# 2019_v1_2.net
KiCad netlist of a schematic drawn in Altium Designer
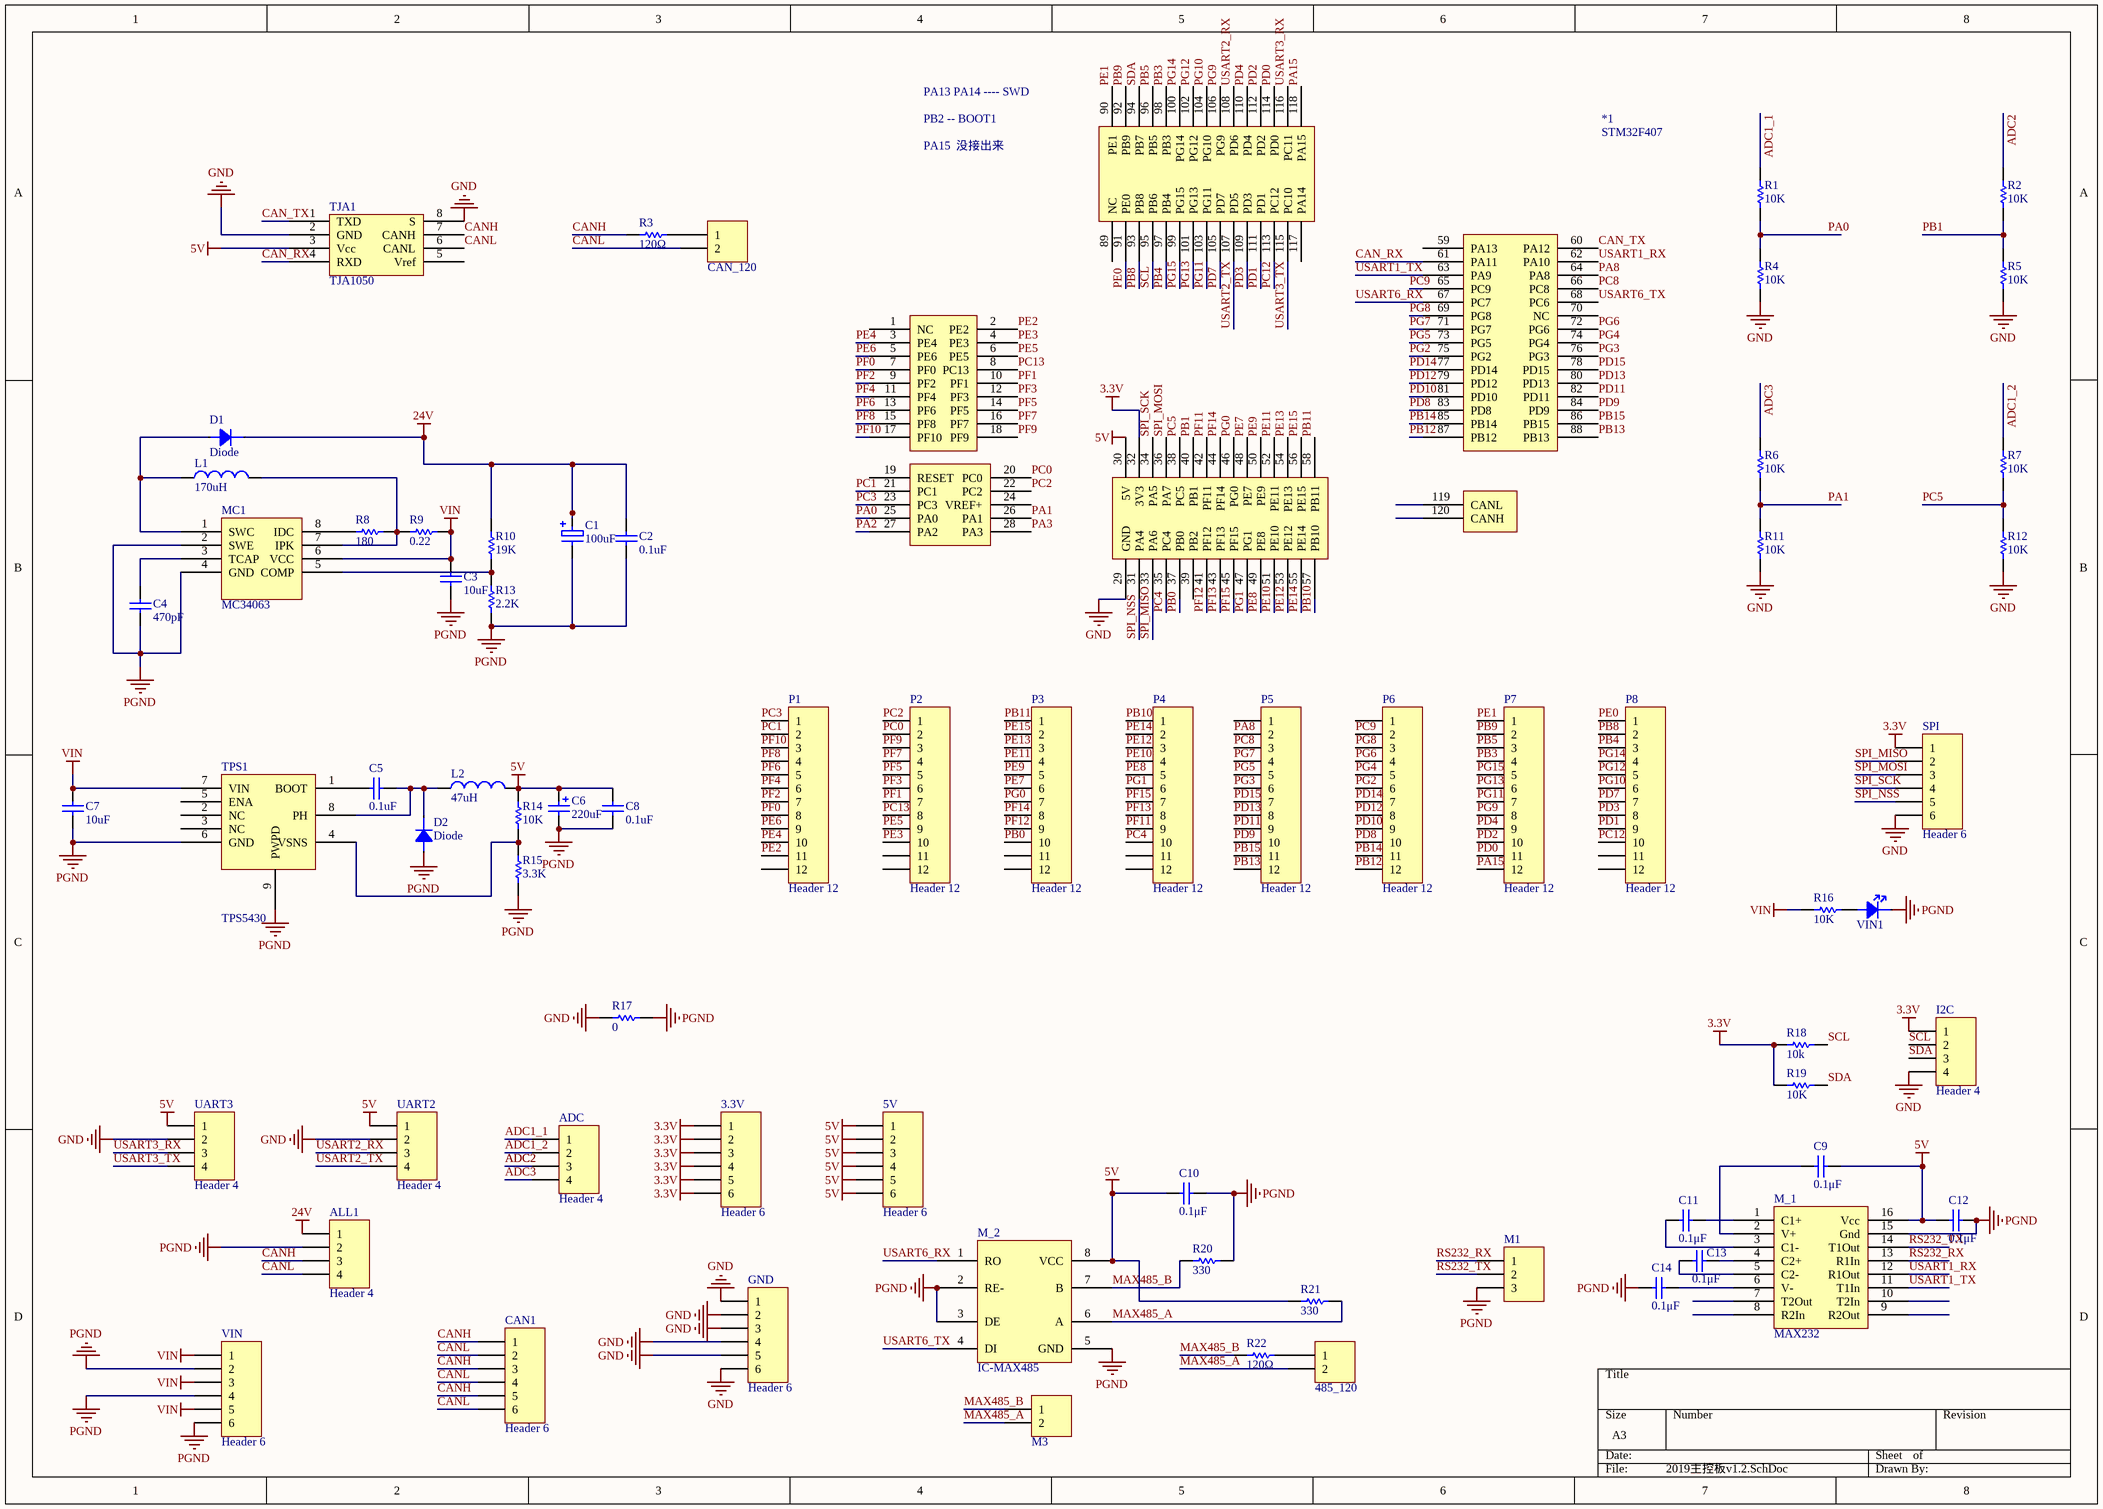
[diagram p0: 2019主控板v1.2.SchDoc]

(export (version "E")
  (design (tool "Eeschema 10.0.6"))
  (components
    (comp (ref "*1")
      (value "STM32F407")
      (footprint "STM32F407")
      (libsource (lib "K60-mainboard-v3.1") (part "STM32F407"))
    )
    (comp (ref "3.3V")
      (value "Header 6")
      (footprint "XH-2.54PIN6")
      (description "Header, 6-Pin")
      (fields (field (name "PUBLISHER") "Altium Limited"))
      (libsource (lib "Libraries_2014_0618") (part "Header 6"))
    )
    (comp (ref "5V")
      (value "Header 6")
      (footprint "XH-2.54PIN6")
      (description "Header, 6-Pin")
      (fields (field (name "PUBLISHER") "Altium Limited"))
      (libsource (lib "Libraries_2014_0618") (part "Header 6"))
    )
    (comp (ref "485_120")
      (value "Header 2")
      (footprint "SIP2")
      (description "Header, 2-Pin")
      (fields (field (name "PUBLISHER") "Altium Limited"))
      (libsource (lib "Libraries_2014_0618") (part "Header 2"))
    )
    (comp (ref "ADC")
      (value "Header 4")
      (footprint "XH-2.54pin4")
      (description "Header, 4-Pin")
      (fields (field (name "PUBLISHER") "Altium Limited"))
      (libsource (lib "Libraries_2014_0618") (part "Header 4"))
    )
    (comp (ref "ALL1")
      (value "Header 4")
      (footprint "XH-2.54pin4")
      (description "Header, 4-Pin")
      (fields (field (name "PUBLISHER") "Altium Limited"))
      (libsource (lib "Libraries_2014_0618") (part "Header 4"))
    )
    (comp (ref "C1")
      (value "100uF")
      (footprint "C_ELE")
      (description "电解电容")
      (fields (field (name "PUBLISHER") "Altium Limited"))
      (libsource (lib "Libraries_2014_0618") (part "CAP-ELE"))
    )
    (comp (ref "C2")
      (value "0.1uF")
      (footprint "CAP-MLCC-0603")
      (description "Capacitor")
      (fields (field (name "Comment") "Cap") (field (name "PUBLISHER") "Altium Limited"))
      (libsource (lib "K60-mainboard-v3.1") (part "Cap"))
    )
    (comp (ref "C3")
      (value "10uF")
      (footprint "0805C")
      (description "Capacitor")
      (fields (field (name "Comment") "Cap") (field (name "PUBLISHER") "Altium Limited"))
      (libsource (lib "K60-mainboard-v3.1") (part "Cap"))
    )
    (comp (ref "C4")
      (value "470pF")
      (footprint "CAP-MLCC-0603")
      (description "Capacitor")
      (fields (field (name "Comment") "Cap") (field (name "PUBLISHER") "Altium Limited"))
      (libsource (lib "K60-mainboard-v3.1") (part "Cap"))
    )
    (comp (ref "C5")
      (value "0.1uF")
      (footprint "CAP-MLCC-0603")
      (description "Capacitor")
      (fields (field (name "Comment") "Cap") (field (name "PUBLISHER") "Altium Limited"))
      (libsource (lib "K60-mainboard-v3.1") (part "Cap"))
    )
    (comp (ref "C6")
      (value "220uF")
      (footprint "CAP-TAN-7343/CAPD")
      (description "Polarized Capacitor (Radial)")
      (fields (field (name "Comment") "Cap Pol1") (field (name "PUBLISHER") "Altium Limited"))
      (libsource (lib "K60-mainboard-v3.1") (part "Cap Pol1"))
    )
    (comp (ref "C7")
      (value "10uF")
      (footprint "0805C")
      (description "Capacitor")
      (fields (field (name "Comment") "Cap") (field (name "PUBLISHER") "Altium Limited"))
      (libsource (lib "K60-mainboard-v3.1") (part "Cap"))
    )
    (comp (ref "C8")
      (value "0.1uF")
      (footprint "CAP-MLCC-0603")
      (description "Capacitor")
      (fields (field (name "Comment") "Cap") (field (name "PUBLISHER") "Altium Limited"))
      (libsource (lib "K60-mainboard-v3.1") (part "Cap"))
    )
    (comp (ref "C9")
      (value "0.1μF")
      (footprint "CAP-MLCC-0603")
      (description "无极性电容")
      (fields (field (name "PUBLISHER") "Altium Limited"))
      (libsource (lib "Libraries_2014_0618") (part "CAP"))
    )
    (comp (ref "C10")
      (value "0.1μF")
      (footprint "CAP-MLCC-0603")
      (description "无极性电容")
      (fields (field (name "PUBLISHER") "Altium Limited"))
      (libsource (lib "Libraries_2014_0618") (part "CAP"))
    )
    (comp (ref "C11")
      (value "0.1μF")
      (footprint "CAP-MLCC-0603")
      (description "无极性电容")
      (fields (field (name "PUBLISHER") "Altium Limited"))
      (libsource (lib "Libraries_2014_0618") (part "CAP"))
    )
    (comp (ref "C12")
      (value "0.1μF")
      (footprint "CAP-MLCC-0603")
      (description "无极性电容")
      (fields (field (name "PUBLISHER") "Altium Limited"))
      (libsource (lib "Libraries_2014_0618") (part "CAP"))
    )
    (comp (ref "C13")
      (value "0.1μF")
      (footprint "CAP-MLCC-0603")
      (description "无极性电容")
      (fields (field (name "PUBLISHER") "Altium Limited"))
      (libsource (lib "Libraries_2014_0618") (part "CAP"))
    )
    (comp (ref "C14")
      (value "0.1μF")
      (footprint "CAP-MLCC-0603")
      (description "无极性电容")
      (fields (field (name "PUBLISHER") "Altium Limited"))
      (libsource (lib "Libraries_2014_0618") (part "CAP"))
    )
    (comp (ref "CAN1")
      (value "Header 6")
      (footprint "Green_6P")
      (description "Header, 6-Pin")
      (fields (field (name "PUBLISHER") "Altium Limited"))
      (libsource (lib "Libraries_2014_0618") (part "Header 6"))
    )
    (comp (ref "CAN_120")
      (value "Header 2")
      (footprint "SIP2")
      (description "Header, 2-Pin")
      (fields (field (name "PUBLISHER") "Altium Limited"))
      (libsource (lib "Libraries_2014_0618") (part "Header 2"))
    )
    (comp (ref "D1") (value "Diode") (footprint "SS34") (libsource (lib "K60-mainboard-v3.1") (part "Diode")))
    (comp (ref "D2") (value "Diode") (footprint "SS34") (libsource (lib "K60-mainboard-v3.1") (part "Diode")))
    (comp (ref "GND")
      (value "Header 6")
      (footprint "XH-2.54PIN6")
      (description "Header, 6-Pin")
      (fields (field (name "PUBLISHER") "Altium Limited"))
      (libsource (lib "Libraries_2014_0618") (part "Header 6"))
    )
    (comp (ref "I2C")
      (value "Header 4")
      (footprint "XH-2.54pin4")
      (description "Header, 4-Pin")
      (fields (field (name "PUBLISHER") "Altium Limited"))
      (libsource (lib "Libraries_2014_0618") (part "Header 4"))
    )
    (comp (ref "L1")
      (value "170uH")
      (footprint "CD74")
      (description "Inductor")
      (fields (field (name "PUBLISHER") "Altium Limited"))
      (libsource (lib "smartcar_example") (part "Inductor"))
    )
    (comp (ref "L2")
      (value "47uH")
      (footprint "CD74")
      (description "Inductor")
      (fields (field (name "PUBLISHER") "Altium Limited"))
      (libsource (lib "smartcar_example") (part "Inductor"))
    )
    (comp (ref "M1")
      (value "Header 3")
      (footprint "Green_3P")
      (description "Header, 3-Pin")
      (fields (field (name "PUBLISHER") "Altium Limited"))
      (libsource (lib "Libraries_2014_0618") (part "Header 3"))
    )
    (comp (ref "M3")
      (value "Header 2")
      (footprint "Green_2P")
      (description "Header, 2-Pin")
      (fields (field (name "PUBLISHER") "Altium Limited"))
      (libsource (lib "Libraries_2014_0618") (part "Header 2"))
    )
    (comp (ref "MC1")
      (value "MC34063")
      (footprint "SO8")
      (libsource (lib "K60-mainboard-v3.1") (part "MC34063"))
    )
    (comp (ref "M_1")
      (value "MAX232")
      (footprint "SO-16_M")
      (libsource (lib "Libraries_2014_0618") (part "IC-MAX232"))
    )
    (comp (ref "M_2")
      (value "IC-MAX485")
      (footprint "SO8_M")
      (description "MAX485")
      (libsource (lib "Libraries_2014_0618") (part "IC-MAX485"))
    )
    (comp (ref "P1")
      (value "Header 12")
      (footprint "XH-2.54PIN12")
      (description "Header, 12-Pin")
      (fields (field (name "PUBLISHER") "Altium Limited"))
      (libsource (lib "Libraries_2014_0618") (part "Header 12"))
    )
    (comp (ref "P2")
      (value "Header 12")
      (footprint "XH-2.54PIN12")
      (description "Header, 12-Pin")
      (fields (field (name "PUBLISHER") "Altium Limited"))
      (libsource (lib "Libraries_2014_0618") (part "Header 12"))
    )
    (comp (ref "P3")
      (value "Header 12")
      (footprint "XH-2.54PIN12")
      (description "Header, 12-Pin")
      (fields (field (name "PUBLISHER") "Altium Limited"))
      (libsource (lib "Libraries_2014_0618") (part "Header 12"))
    )
    (comp (ref "P4")
      (value "Header 12")
      (footprint "XH-2.54PIN12")
      (description "Header, 12-Pin")
      (fields (field (name "PUBLISHER") "Altium Limited"))
      (libsource (lib "Libraries_2014_0618") (part "Header 12"))
    )
    (comp (ref "P5")
      (value "Header 12")
      (footprint "XH-2.54PIN12")
      (description "Header, 12-Pin")
      (fields (field (name "PUBLISHER") "Altium Limited"))
      (libsource (lib "Libraries_2014_0618") (part "Header 12"))
    )
    (comp (ref "P6")
      (value "Header 12")
      (footprint "XH-2.54PIN12")
      (description "Header, 12-Pin")
      (fields (field (name "PUBLISHER") "Altium Limited"))
      (libsource (lib "Libraries_2014_0618") (part "Header 12"))
    )
    (comp (ref "P7")
      (value "Header 12")
      (footprint "XH-2.54PIN12")
      (description "Header, 12-Pin")
      (fields (field (name "PUBLISHER") "Altium Limited"))
      (libsource (lib "Libraries_2014_0618") (part "Header 12"))
    )
    (comp (ref "P8")
      (value "Header 12")
      (footprint "XH-2.54PIN12")
      (description "Header, 12-Pin")
      (fields (field (name "PUBLISHER") "Altium Limited"))
      (libsource (lib "Libraries_2014_0618") (part "Header 12"))
    )
    (comp (ref "R1")
      (value "10K")
      (footprint "RES-0603")
      (description "Resistor")
      (fields (field (name "Comment") "Res1") (field (name "PUBLISHER") "Altium Limited"))
      (libsource (lib "K60-mainboard-v3.1") (part "Res1"))
    )
    (comp (ref "R2")
      (value "10K")
      (footprint "RES-0603")
      (description "Resistor")
      (fields (field (name "Comment") "Res1") (field (name "PUBLISHER") "Altium Limited"))
      (libsource (lib "K60-mainboard-v3.1") (part "Res1"))
    )
    (comp (ref "R3")
      (value "120Ω")
      (footprint "RES-0603")
      (description "电阻")
      (fields (field (name "PUBLISHER") "Altium Limited"))
      (libsource (lib "Libraries_2014_0618") (part "RES"))
    )
    (comp (ref "R4")
      (value "10K")
      (footprint "RES-0603")
      (description "Resistor")
      (fields (field (name "Comment") "Res1") (field (name "PUBLISHER") "Altium Limited"))
      (libsource (lib "K60-mainboard-v3.1") (part "Res1"))
    )
    (comp (ref "R5")
      (value "10K")
      (footprint "RES-0603")
      (description "Resistor")
      (fields (field (name "Comment") "Res1") (field (name "PUBLISHER") "Altium Limited"))
      (libsource (lib "K60-mainboard-v3.1") (part "Res1"))
    )
    (comp (ref "R6")
      (value "10K")
      (footprint "RES-0603")
      (description "Resistor")
      (fields (field (name "Comment") "Res1") (field (name "PUBLISHER") "Altium Limited"))
      (libsource (lib "K60-mainboard-v3.1") (part "Res1"))
    )
    (comp (ref "R7")
      (value "10K")
      (footprint "RES-0603")
      (description "Resistor")
      (fields (field (name "Comment") "Res1") (field (name "PUBLISHER") "Altium Limited"))
      (libsource (lib "K60-mainboard-v3.1") (part "Res1"))
    )
    (comp (ref "R8")
      (value "180")
      (footprint "RES-0603")
      (description "Resistor")
      (fields (field (name "Comment") "Res1") (field (name "PUBLISHER") "Altium Limited"))
      (libsource (lib "K60-mainboard-v3.1") (part "Res1"))
    )
    (comp (ref "R9")
      (value "0.22")
      (footprint "RES-0603")
      (description "Resistor")
      (fields (field (name "Comment") "Res1") (field (name "PUBLISHER") "Altium Limited"))
      (libsource (lib "K60-mainboard-v3.1") (part "Res1"))
    )
    (comp (ref "R10")
      (value "19K")
      (footprint "RES-0603")
      (description "Resistor")
      (fields (field (name "Comment") "Res1") (field (name "PUBLISHER") "Altium Limited"))
      (libsource (lib "K60-mainboard-v3.1") (part "Res1"))
    )
    (comp (ref "R11")
      (value "10K")
      (footprint "RES-0603")
      (description "Resistor")
      (fields (field (name "Comment") "Res1") (field (name "PUBLISHER") "Altium Limited"))
      (libsource (lib "K60-mainboard-v3.1") (part "Res1"))
    )
    (comp (ref "R12")
      (value "10K")
      (footprint "RES-0603")
      (description "Resistor")
      (fields (field (name "Comment") "Res1") (field (name "PUBLISHER") "Altium Limited"))
      (libsource (lib "K60-mainboard-v3.1") (part "Res1"))
    )
    (comp (ref "R13")
      (value "2.2K")
      (footprint "RES-0603")
      (description "Resistor")
      (fields (field (name "Comment") "Res1") (field (name "PUBLISHER") "Altium Limited"))
      (libsource (lib "K60-mainboard-v3.1") (part "Res1"))
    )
    (comp (ref "R14")
      (value "10K")
      (footprint "RES-0603")
      (description "Resistor")
      (fields (field (name "Comment") "Res1") (field (name "PUBLISHER") "Altium Limited"))
      (libsource (lib "K60-mainboard-v3.1") (part "Res1"))
    )
    (comp (ref "R15")
      (value "3.3K")
      (footprint "RES-0603")
      (description "Resistor")
      (fields (field (name "Comment") "Res1") (field (name "PUBLISHER") "Altium Limited"))
      (libsource (lib "K60-mainboard-v3.1") (part "Res1"))
    )
    (comp (ref "R16")
      (value "10K")
      (footprint "RES-0603")
      (description "Resistor")
      (fields (field (name "Comment") "Res1") (field (name "PUBLISHER") "Altium Limited"))
      (libsource (lib "K60-mainboard-v3.1") (part "Res1"))
    )
    (comp (ref "R17")
      (value "0")
      (footprint "RES-0603")
      (description "Resistor")
      (fields (field (name "Comment") "Res1") (field (name "PUBLISHER") "Altium Limited"))
      (libsource (lib "K60-mainboard-v3.1") (part "Res1"))
    )
    (comp (ref "R18")
      (value "10k")
      (footprint "RES-0603")
      (description "电阻")
      (fields (field (name "PUBLISHER") "Altium Limited"))
      (libsource (lib "Libraries_2014_0618") (part "RES"))
    )
    (comp (ref "R19")
      (value "10K")
      (footprint "RES-0603")
      (description "电阻")
      (fields (field (name "PUBLISHER") "Altium Limited"))
      (libsource (lib "Libraries_2014_0618") (part "RES"))
    )
    (comp (ref "R20")
      (value "330")
      (footprint "RES-0603")
      (description "电阻")
      (fields (field (name "PUBLISHER") "Altium Limited"))
      (libsource (lib "Libraries_2014_0618") (part "RES"))
    )
    (comp (ref "R21")
      (value "330")
      (footprint "RES-0603")
      (description "电阻")
      (fields (field (name "PUBLISHER") "Altium Limited"))
      (libsource (lib "Libraries_2014_0618") (part "RES"))
    )
    (comp (ref "R22")
      (value "120Ω")
      (footprint "RES-0603")
      (description "电阻")
      (fields (field (name "PUBLISHER") "Altium Limited"))
      (libsource (lib "Libraries_2014_0618") (part "RES"))
    )
    (comp (ref "SPI")
      (value "Header 6")
      (footprint "XH-2.54PIN6")
      (description "Header, 6-Pin")
      (fields (field (name "PUBLISHER") "Altium Limited"))
      (libsource (lib "Libraries_2014_0618") (part "Header 6"))
    )
    (comp (ref "TJA1")
      (value "TJA1050")
      (footprint "TJA1050")
      (description "CAN总线收发器")
      (libsource (lib "Libraries_2014_0618") (part "TJA1050"))
    )
    (comp (ref "TPS1")
      (value "TPS5430")
      (footprint "TPS5430")
      (libsource (lib "K60-mainboard-v3.1") (part "TPS5430"))
    )
    (comp (ref "UART2")
      (value "Header 4")
      (footprint "HDR1X4")
      (description "Header, 4-Pin")
      (fields (field (name "PUBLISHER") "Altium Limited"))
      (libsource (lib "Libraries_2014_0618") (part "Header 4"))
    )
    (comp (ref "UART3")
      (value "Header 4")
      (footprint "HDR1X4")
      (description "Header, 4-Pin")
      (fields (field (name "PUBLISHER") "Altium Limited"))
      (libsource (lib "Libraries_2014_0618") (part "Header 4"))
    )
    (comp (ref "VIN")
      (value "Header 6")
      (footprint "Green_6P")
      (description "Header, 6-Pin")
      (fields (field (name "PUBLISHER") "Altium Limited"))
      (libsource (lib "Libraries_2014_0618") (part "Header 6"))
    )
    (comp (ref "VIN1")
      (value "lED")
      (footprint "0805D")
      (description "LED")
      (libsource (lib "K60-mainboard-v3.1") (part "00-D-LED"))
    )
  )
  (nets
    (net (code "1") (name "/ADC1_1") (class "Default")
      (node (ref "ADC") (pin "1") (pinfunction "1_1") (pintype "passive"))
      (node (ref "R1") (pin "2") (pinfunction "2_2") (pintype "passive"))
    )
    (net (code "2") (name "/ADC1_2") (class "Default")
      (node (ref "ADC") (pin "2") (pinfunction "2_2") (pintype "passive"))
      (node (ref "R7") (pin "2") (pinfunction "2_2") (pintype "passive"))
    )
    (net (code "3") (name "/ADC2") (class "Default")
      (node (ref "ADC") (pin "3") (pinfunction "3_3") (pintype "passive"))
      (node (ref "R2") (pin "2") (pinfunction "2_2") (pintype "passive"))
    )
    (net (code "4") (name "/ADC3") (class "Default")
      (node (ref "ADC") (pin "4") (pinfunction "4_4") (pintype "passive"))
      (node (ref "R6") (pin "2") (pinfunction "2_2") (pintype "passive"))
    )
    (net (code "5") (name "/CANH") (class "Default")
      (node (ref "ALL1") (pin "3") (pinfunction "3_3") (pintype "passive"))
      (node (ref "CAN1") (pin "1") (pinfunction "1_1") (pintype "passive"))
      (node (ref "CAN1") (pin "3") (pinfunction "3_3") (pintype "passive"))
      (node (ref "CAN1") (pin "5") (pinfunction "5_5") (pintype "passive"))
      (node (ref "R3") (pin "2") (pinfunction "2_2") (pintype "passive"))
      (node (ref "TJA1") (pin "7") (pinfunction "CANH_7") (pintype "passive"))
    )
    (net (code "6") (name "/CANL") (class "Default")
      (node (ref "ALL1") (pin "4") (pinfunction "4_4") (pintype "passive"))
      (node (ref "CAN1") (pin "2") (pinfunction "2_2") (pintype "passive"))
      (node (ref "CAN1") (pin "4") (pinfunction "4_4") (pintype "passive"))
      (node (ref "CAN1") (pin "6") (pinfunction "6_6") (pintype "passive"))
      (node (ref "CAN_120") (pin "2") (pinfunction "2_2") (pintype "passive"))
      (node (ref "TJA1") (pin "6") (pinfunction "CANL_6") (pintype "passive"))
    )
    (net (code "7") (name "/CAN_RX") (class "Default")
      (node (ref "*1") (pin "61") (pinfunction "PA11_61") (pintype "passive"))
      (node (ref "TJA1") (pin "4") (pinfunction "RXD_4") (pintype "passive"))
    )
    (net (code "8") (name "/CAN_TX") (class "Default")
      (node (ref "*1") (pin "60") (pinfunction "PA12_60") (pintype "passive"))
      (node (ref "TJA1") (pin "1") (pinfunction "TXD_1") (pintype "passive"))
    )
    (net (code "9") (name "/MAX485_A") (class "Default")
      (node (ref "485_120") (pin "2") (pinfunction "2_2") (pintype "passive"))
      (node (ref "M3") (pin "2") (pinfunction "2_2") (pintype "passive"))
      (node (ref "M_2") (pin "6") (pinfunction "A_6") (pintype "passive"))
      (node (ref "R21") (pin "1") (pinfunction "1_1") (pintype "passive"))
    )
    (net (code "10") (name "/MAX485_B") (class "Default")
      (node (ref "M3") (pin "1") (pinfunction "1_1") (pintype "passive"))
      (node (ref "M_2") (pin "7") (pinfunction "B_7") (pintype "passive"))
      (node (ref "R20") (pin "2") (pinfunction "2_2") (pintype "passive"))
      (node (ref "R22") (pin "2") (pinfunction "2_2") (pintype "passive"))
    )
    (net (code "11") (name "/PA0") (class "Default")
      (node (ref "*1") (pin "25") (pinfunction "PA0_25") (pintype "passive"))
      (node (ref "R1") (pin "1") (pinfunction "1_1") (pintype "passive"))
      (node (ref "R4") (pin "2") (pinfunction "2_2") (pintype "passive"))
    )
    (net (code "12") (name "/PA1") (class "Default")
      (node (ref "*1") (pin "26") (pinfunction "PA1_26") (pintype "passive"))
      (node (ref "R11") (pin "2") (pinfunction "2_2") (pintype "passive"))
      (node (ref "R6") (pin "1") (pinfunction "1_1") (pintype "passive"))
    )
    (net (code "13") (name "/PA2") (class "Default")
      (node (ref "*1") (pin "27") (pinfunction "PA2_27") (pintype "passive"))
    )
    (net (code "14") (name "/PA3") (class "Default")
      (node (ref "*1") (pin "28") (pinfunction "PA3_28") (pintype "passive"))
    )
    (net (code "15") (name "/PA8") (class "Default")
      (node (ref "*1") (pin "64") (pinfunction "PA8_64") (pintype "passive"))
      (node (ref "P5") (pin "2") (pinfunction "2_2") (pintype "passive"))
    )
    (net (code "16") (name "/PA15") (class "Default")
      (node (ref "*1") (pin "118") (pinfunction "PA15_118") (pintype "passive"))
      (node (ref "P7") (pin "12") (pinfunction "12_12") (pintype "passive"))
    )
    (net (code "17") (name "/PB0") (class "Default")
      (node (ref "*1") (pin "37") (pinfunction "PB0_37") (pintype "passive"))
      (node (ref "P3") (pin "10") (pinfunction "10_10") (pintype "passive"))
    )
    (net (code "18") (name "/PB1") (class "Default")
      (node (ref "*1") (pin "40") (pinfunction "PB1_40") (pintype "passive"))
      (node (ref "R2") (pin "1") (pinfunction "1_1") (pintype "passive"))
      (node (ref "R5") (pin "2") (pinfunction "2_2") (pintype "passive"))
    )
    (net (code "19") (name "/PB3") (class "Default")
      (node (ref "*1") (pin "98") (pinfunction "PB3_98") (pintype "passive"))
      (node (ref "P7") (pin "4") (pinfunction "4_4") (pintype "passive"))
    )
    (net (code "20") (name "/PB4") (class "Default")
      (node (ref "*1") (pin "97") (pinfunction "PB4_97") (pintype "passive"))
      (node (ref "P8") (pin "3") (pinfunction "3_3") (pintype "passive"))
    )
    (net (code "21") (name "/PB5") (class "Default")
      (node (ref "*1") (pin "96") (pinfunction "PB5_96") (pintype "passive"))
      (node (ref "P7") (pin "3") (pinfunction "3_3") (pintype "passive"))
    )
    (net (code "22") (name "/PB8") (class "Default")
      (node (ref "*1") (pin "93") (pinfunction "PB8_93") (pintype "passive"))
      (node (ref "P8") (pin "2") (pinfunction "2_2") (pintype "passive"))
    )
    (net (code "23") (name "/PB9") (class "Default")
      (node (ref "*1") (pin "92") (pinfunction "PB9_92") (pintype "passive"))
      (node (ref "P7") (pin "2") (pinfunction "2_2") (pintype "passive"))
    )
    (net (code "24") (name "/PB10") (class "Default")
      (node (ref "*1") (pin "57") (pinfunction "PB10_57") (pintype "passive"))
      (node (ref "P4") (pin "1") (pinfunction "1_1") (pintype "passive"))
    )
    (net (code "25") (name "/PB11") (class "Default")
      (node (ref "*1") (pin "58") (pinfunction "PB11_58") (pintype "passive"))
      (node (ref "P3") (pin "1") (pinfunction "1_1") (pintype "passive"))
    )
    (net (code "26") (name "/PB12") (class "Default")
      (node (ref "*1") (pin "87") (pinfunction "PB12_87") (pintype "passive"))
      (node (ref "P6") (pin "12") (pinfunction "12_12") (pintype "passive"))
    )
    (net (code "27") (name "/PB13") (class "Default")
      (node (ref "*1") (pin "88") (pinfunction "PB13_88") (pintype "passive"))
      (node (ref "P5") (pin "12") (pinfunction "12_12") (pintype "passive"))
    )
    (net (code "28") (name "/PB14") (class "Default")
      (node (ref "*1") (pin "85") (pinfunction "PB14_85") (pintype "passive"))
      (node (ref "P6") (pin "11") (pinfunction "11_11") (pintype "passive"))
    )
    (net (code "29") (name "/PB15") (class "Default")
      (node (ref "*1") (pin "86") (pinfunction "PB15_86") (pintype "passive"))
      (node (ref "P5") (pin "11") (pinfunction "11_11") (pintype "passive"))
    )
    (net (code "30") (name "/PC0") (class "Default")
      (node (ref "*1") (pin "20") (pinfunction "PC0_20") (pintype "passive"))
      (node (ref "P2") (pin "2") (pinfunction "2_2") (pintype "passive"))
    )
    (net (code "31") (name "/PC1") (class "Default")
      (node (ref "*1") (pin "21") (pinfunction "PC1_21") (pintype "passive"))
      (node (ref "P1") (pin "2") (pinfunction "2_2") (pintype "passive"))
    )
    (net (code "32") (name "/PC2") (class "Default")
      (node (ref "*1") (pin "22") (pinfunction "PC2_22") (pintype "passive"))
      (node (ref "P2") (pin "1") (pinfunction "1_1") (pintype "passive"))
    )
    (net (code "33") (name "/PC3") (class "Default")
      (node (ref "*1") (pin "23") (pinfunction "PC3_23") (pintype "passive"))
      (node (ref "P1") (pin "1") (pinfunction "1_1") (pintype "passive"))
    )
    (net (code "34") (name "/PC4") (class "Default")
      (node (ref "*1") (pin "35") (pinfunction "PC4_35") (pintype "passive"))
      (node (ref "P4") (pin "10") (pinfunction "10_10") (pintype "passive"))
    )
    (net (code "35") (name "/PC5") (class "Default")
      (node (ref "*1") (pin "38") (pinfunction "PC5_38") (pintype "passive"))
      (node (ref "R12") (pin "2") (pinfunction "2_2") (pintype "passive"))
      (node (ref "R7") (pin "1") (pinfunction "1_1") (pintype "passive"))
    )
    (net (code "36") (name "/PC8") (class "Default")
      (node (ref "*1") (pin "66") (pinfunction "PC8_66") (pintype "passive"))
      (node (ref "P5") (pin "3") (pinfunction "3_3") (pintype "passive"))
    )
    (net (code "37") (name "/PC9") (class "Default")
      (node (ref "*1") (pin "65") (pinfunction "PC9_65") (pintype "passive"))
      (node (ref "P6") (pin "2") (pinfunction "2_2") (pintype "passive"))
    )
    (net (code "38") (name "/PC12") (class "Default")
      (node (ref "*1") (pin "113") (pinfunction "PC12_113") (pintype "passive"))
      (node (ref "P8") (pin "10") (pinfunction "10_10") (pintype "passive"))
    )
    (net (code "39") (name "/PC13") (class "Default")
      (node (ref "*1") (pin "8") (pinfunction "PC13_8") (pintype "passive"))
      (node (ref "P2") (pin "8") (pinfunction "8_8") (pintype "passive"))
    )
    (net (code "40") (name "/PD0") (class "Default")
      (node (ref "*1") (pin "114") (pinfunction "PD0_114") (pintype "passive"))
      (node (ref "P7") (pin "11") (pinfunction "11_11") (pintype "passive"))
    )
    (net (code "41") (name "/PD1") (class "Default")
      (node (ref "*1") (pin "111") (pinfunction "PD1_111") (pintype "passive"))
      (node (ref "P8") (pin "9") (pinfunction "9_9") (pintype "passive"))
    )
    (net (code "42") (name "/PD2") (class "Default")
      (node (ref "*1") (pin "112") (pinfunction "PD2_112") (pintype "passive"))
      (node (ref "P7") (pin "10") (pinfunction "10_10") (pintype "passive"))
    )
    (net (code "43") (name "/PD3") (class "Default")
      (node (ref "*1") (pin "109") (pinfunction "PD3_109") (pintype "passive"))
      (node (ref "P8") (pin "8") (pinfunction "8_8") (pintype "passive"))
    )
    (net (code "44") (name "/PD4") (class "Default")
      (node (ref "*1") (pin "110") (pinfunction "PD4_110") (pintype "passive"))
      (node (ref "P7") (pin "9") (pinfunction "9_9") (pintype "passive"))
    )
    (net (code "45") (name "/PD7") (class "Default")
      (node (ref "*1") (pin "105") (pinfunction "PD7_105") (pintype "passive"))
      (node (ref "P8") (pin "7") (pinfunction "7_7") (pintype "passive"))
    )
    (net (code "46") (name "/PD8") (class "Default")
      (node (ref "*1") (pin "83") (pinfunction "PD8_83") (pintype "passive"))
      (node (ref "P6") (pin "10") (pinfunction "10_10") (pintype "passive"))
    )
    (net (code "47") (name "/PD9") (class "Default")
      (node (ref "*1") (pin "84") (pinfunction "PD9_84") (pintype "passive"))
      (node (ref "P5") (pin "10") (pinfunction "10_10") (pintype "passive"))
    )
    (net (code "48") (name "/PD10") (class "Default")
      (node (ref "*1") (pin "81") (pinfunction "PD10_81") (pintype "passive"))
      (node (ref "P6") (pin "9") (pinfunction "9_9") (pintype "passive"))
    )
    (net (code "49") (name "/PD11") (class "Default")
      (node (ref "*1") (pin "82") (pinfunction "PD11_82") (pintype "passive"))
      (node (ref "P5") (pin "9") (pinfunction "9_9") (pintype "passive"))
    )
    (net (code "50") (name "/PD12") (class "Default")
      (node (ref "*1") (pin "79") (pinfunction "PD12_79") (pintype "passive"))
      (node (ref "P6") (pin "8") (pinfunction "8_8") (pintype "passive"))
    )
    (net (code "51") (name "/PD13") (class "Default")
      (node (ref "*1") (pin "80") (pinfunction "PD13_80") (pintype "passive"))
      (node (ref "P5") (pin "8") (pinfunction "8_8") (pintype "passive"))
    )
    (net (code "52") (name "/PD14") (class "Default")
      (node (ref "*1") (pin "77") (pinfunction "PD14_77") (pintype "passive"))
      (node (ref "P6") (pin "7") (pinfunction "7_7") (pintype "passive"))
    )
    (net (code "53") (name "/PD15") (class "Default")
      (node (ref "*1") (pin "78") (pinfunction "PD15_78") (pintype "passive"))
      (node (ref "P5") (pin "7") (pinfunction "7_7") (pintype "passive"))
    )
    (net (code "54") (name "/PE0") (class "Default")
      (node (ref "*1") (pin "91") (pinfunction "PE0_91") (pintype "passive"))
      (node (ref "P8") (pin "1") (pinfunction "1_1") (pintype "passive"))
    )
    (net (code "55") (name "/PE1") (class "Default")
      (node (ref "*1") (pin "90") (pinfunction "PE1_90") (pintype "passive"))
      (node (ref "P7") (pin "1") (pinfunction "1_1") (pintype "passive"))
    )
    (net (code "56") (name "/PE2") (class "Default")
      (node (ref "*1") (pin "2") (pinfunction "PE2_2") (pintype "passive"))
      (node (ref "P1") (pin "11") (pinfunction "11_11") (pintype "passive"))
    )
    (net (code "57") (name "/PE3") (class "Default")
      (node (ref "*1") (pin "4") (pinfunction "PE3_4") (pintype "passive"))
      (node (ref "P2") (pin "10") (pinfunction "10_10") (pintype "passive"))
    )
    (net (code "58") (name "/PE4") (class "Default")
      (node (ref "*1") (pin "3") (pinfunction "PE4_3") (pintype "passive"))
      (node (ref "P1") (pin "10") (pinfunction "10_10") (pintype "passive"))
    )
    (net (code "59") (name "/PE5") (class "Default")
      (node (ref "*1") (pin "6") (pinfunction "PE5_6") (pintype "passive"))
      (node (ref "P2") (pin "9") (pinfunction "9_9") (pintype "passive"))
    )
    (net (code "60") (name "/PE6") (class "Default")
      (node (ref "*1") (pin "5") (pinfunction "PE6_5") (pintype "passive"))
      (node (ref "P1") (pin "9") (pinfunction "9_9") (pintype "passive"))
    )
    (net (code "61") (name "/PE7") (class "Default")
      (node (ref "*1") (pin "48") (pinfunction "PE7_48") (pintype "passive"))
      (node (ref "P3") (pin "6") (pinfunction "6_6") (pintype "passive"))
    )
    (net (code "62") (name "/PE8") (class "Default")
      (node (ref "*1") (pin "49") (pinfunction "PE8_49") (pintype "passive"))
      (node (ref "P4") (pin "5") (pinfunction "5_5") (pintype "passive"))
    )
    (net (code "63") (name "/PE9") (class "Default")
      (node (ref "*1") (pin "50") (pinfunction "PE9_50") (pintype "passive"))
      (node (ref "P3") (pin "5") (pinfunction "5_5") (pintype "passive"))
    )
    (net (code "64") (name "/PE10") (class "Default")
      (node (ref "*1") (pin "51") (pinfunction "PE10_51") (pintype "passive"))
      (node (ref "P4") (pin "4") (pinfunction "4_4") (pintype "passive"))
    )
    (net (code "65") (name "/PE11") (class "Default")
      (node (ref "*1") (pin "52") (pinfunction "PE11_52") (pintype "passive"))
      (node (ref "P3") (pin "4") (pinfunction "4_4") (pintype "passive"))
    )
    (net (code "66") (name "/PE12") (class "Default")
      (node (ref "*1") (pin "53") (pinfunction "PE12_53") (pintype "passive"))
      (node (ref "P4") (pin "3") (pinfunction "3_3") (pintype "passive"))
    )
    (net (code "67") (name "/PE13") (class "Default")
      (node (ref "*1") (pin "54") (pinfunction "PE13_54") (pintype "passive"))
      (node (ref "P3") (pin "3") (pinfunction "3_3") (pintype "passive"))
    )
    (net (code "68") (name "/PE14") (class "Default")
      (node (ref "*1") (pin "55") (pinfunction "PE14_55") (pintype "passive"))
      (node (ref "P4") (pin "2") (pinfunction "2_2") (pintype "passive"))
    )
    (net (code "69") (name "/PE15") (class "Default")
      (node (ref "*1") (pin "56") (pinfunction "PE15_56") (pintype "passive"))
      (node (ref "P3") (pin "2") (pinfunction "2_2") (pintype "passive"))
    )
    (net (code "70") (name "/PF0") (class "Default")
      (node (ref "*1") (pin "7") (pinfunction "PF0_7") (pintype "passive"))
      (node (ref "P1") (pin "8") (pinfunction "8_8") (pintype "passive"))
    )
    (net (code "71") (name "/PF1") (class "Default")
      (node (ref "*1") (pin "10") (pinfunction "PF1_10") (pintype "passive"))
      (node (ref "P2") (pin "7") (pinfunction "7_7") (pintype "passive"))
    )
    (net (code "72") (name "/PF2") (class "Default")
      (node (ref "*1") (pin "9") (pinfunction "PF2_9") (pintype "passive"))
      (node (ref "P1") (pin "7") (pinfunction "7_7") (pintype "passive"))
    )
    (net (code "73") (name "/PF3") (class "Default")
      (node (ref "*1") (pin "12") (pinfunction "PF3_12") (pintype "passive"))
      (node (ref "P2") (pin "6") (pinfunction "6_6") (pintype "passive"))
    )
    (net (code "74") (name "/PF4") (class "Default")
      (node (ref "*1") (pin "11") (pinfunction "PF4_11") (pintype "passive"))
      (node (ref "P1") (pin "6") (pinfunction "6_6") (pintype "passive"))
    )
    (net (code "75") (name "/PF5") (class "Default")
      (node (ref "*1") (pin "14") (pinfunction "PF5_14") (pintype "passive"))
      (node (ref "P2") (pin "5") (pinfunction "5_5") (pintype "passive"))
    )
    (net (code "76") (name "/PF6") (class "Default")
      (node (ref "*1") (pin "13") (pinfunction "PF6_13") (pintype "passive"))
      (node (ref "P1") (pin "5") (pinfunction "5_5") (pintype "passive"))
    )
    (net (code "77") (name "/PF7") (class "Default")
      (node (ref "*1") (pin "16") (pinfunction "PF7_16") (pintype "passive"))
      (node (ref "P2") (pin "4") (pinfunction "4_4") (pintype "passive"))
    )
    (net (code "78") (name "/PF8") (class "Default")
      (node (ref "*1") (pin "15") (pinfunction "PF8_15") (pintype "passive"))
      (node (ref "P1") (pin "4") (pinfunction "4_4") (pintype "passive"))
    )
    (net (code "79") (name "/PF9") (class "Default")
      (node (ref "*1") (pin "18") (pinfunction "PF9_18") (pintype "passive"))
      (node (ref "P2") (pin "3") (pinfunction "3_3") (pintype "passive"))
    )
    (net (code "80") (name "/PF10") (class "Default")
      (node (ref "*1") (pin "17") (pinfunction "PF10_17") (pintype "passive"))
      (node (ref "P1") (pin "3") (pinfunction "3_3") (pintype "passive"))
    )
    (net (code "81") (name "/PF11") (class "Default")
      (node (ref "*1") (pin "42") (pinfunction "PF11_42") (pintype "passive"))
      (node (ref "P4") (pin "9") (pinfunction "9_9") (pintype "passive"))
    )
    (net (code "82") (name "/PF12") (class "Default")
      (node (ref "*1") (pin "41") (pinfunction "PF12_41") (pintype "passive"))
      (node (ref "P3") (pin "9") (pinfunction "9_9") (pintype "passive"))
    )
    (net (code "83") (name "/PF13") (class "Default")
      (node (ref "*1") (pin "43") (pinfunction "PF13_43") (pintype "passive"))
      (node (ref "P4") (pin "8") (pinfunction "8_8") (pintype "passive"))
    )
    (net (code "84") (name "/PF14") (class "Default")
      (node (ref "*1") (pin "44") (pinfunction "PF14_44") (pintype "passive"))
      (node (ref "P3") (pin "8") (pinfunction "8_8") (pintype "passive"))
    )
    (net (code "85") (name "/PF15") (class "Default")
      (node (ref "*1") (pin "45") (pinfunction "PF15_45") (pintype "passive"))
      (node (ref "P4") (pin "7") (pinfunction "7_7") (pintype "passive"))
    )
    (net (code "86") (name "/PG0") (class "Default")
      (node (ref "*1") (pin "46") (pinfunction "PG0_46") (pintype "passive"))
      (node (ref "P3") (pin "7") (pinfunction "7_7") (pintype "passive"))
    )
    (net (code "87") (name "/PG1") (class "Default")
      (node (ref "*1") (pin "47") (pinfunction "PG1_47") (pintype "passive"))
      (node (ref "P4") (pin "6") (pinfunction "6_6") (pintype "passive"))
    )
    (net (code "88") (name "/PG2") (class "Default")
      (node (ref "*1") (pin "75") (pinfunction "PG2_75") (pintype "passive"))
      (node (ref "P6") (pin "6") (pinfunction "6_6") (pintype "passive"))
    )
    (net (code "89") (name "/PG3") (class "Default")
      (node (ref "*1") (pin "76") (pinfunction "PG3_76") (pintype "passive"))
      (node (ref "P5") (pin "6") (pinfunction "6_6") (pintype "passive"))
    )
    (net (code "90") (name "/PG4") (class "Default")
      (node (ref "*1") (pin "74") (pinfunction "PG4_74") (pintype "passive"))
      (node (ref "P6") (pin "5") (pinfunction "5_5") (pintype "passive"))
    )
    (net (code "91") (name "/PG5") (class "Default")
      (node (ref "*1") (pin "73") (pinfunction "PG5_73") (pintype "passive"))
      (node (ref "P5") (pin "5") (pinfunction "5_5") (pintype "passive"))
    )
    (net (code "92") (name "/PG6") (class "Default")
      (node (ref "*1") (pin "72") (pinfunction "PG6_72") (pintype "passive"))
      (node (ref "P6") (pin "4") (pinfunction "4_4") (pintype "passive"))
    )
    (net (code "93") (name "/PG7") (class "Default")
      (node (ref "*1") (pin "71") (pinfunction "PG7_71") (pintype "passive"))
      (node (ref "P5") (pin "4") (pinfunction "4_4") (pintype "passive"))
    )
    (net (code "94") (name "/PG8") (class "Default")
      (node (ref "*1") (pin "69") (pinfunction "PG8_69") (pintype "passive"))
      (node (ref "P6") (pin "3") (pinfunction "3_3") (pintype "passive"))
    )
    (net (code "95") (name "/PG9") (class "Default")
      (node (ref "*1") (pin "106") (pinfunction "PG9_106") (pintype "passive"))
      (node (ref "P7") (pin "8") (pinfunction "8_8") (pintype "passive"))
    )
    (net (code "96") (name "/PG10") (class "Default")
      (node (ref "*1") (pin "104") (pinfunction "PG10_104") (pintype "passive"))
      (node (ref "P8") (pin "6") (pinfunction "6_6") (pintype "passive"))
    )
    (net (code "97") (name "/PG11") (class "Default")
      (node (ref "*1") (pin "103") (pinfunction "PG11_103") (pintype "passive"))
      (node (ref "P7") (pin "7") (pinfunction "7_7") (pintype "passive"))
    )
    (net (code "98") (name "/PG12") (class "Default")
      (node (ref "*1") (pin "102") (pinfunction "PG12_102") (pintype "passive"))
      (node (ref "P8") (pin "5") (pinfunction "5_5") (pintype "passive"))
    )
    (net (code "99") (name "/PG13") (class "Default")
      (node (ref "*1") (pin "101") (pinfunction "PG13_101") (pintype "passive"))
      (node (ref "P7") (pin "6") (pinfunction "6_6") (pintype "passive"))
    )
    (net (code "100") (name "/PG14") (class "Default")
      (node (ref "*1") (pin "100") (pinfunction "PG14_100") (pintype "passive"))
      (node (ref "P8") (pin "4") (pinfunction "4_4") (pintype "passive"))
    )
    (net (code "101") (name "/PG15") (class "Default")
      (node (ref "*1") (pin "99") (pinfunction "PG15_99") (pintype "passive"))
      (node (ref "P7") (pin "5") (pinfunction "5_5") (pintype "passive"))
    )
    (net (code "102") (name "/RS232_RX") (class "Default")
      (node (ref "M1") (pin "1") (pinfunction "1_1") (pintype "passive"))
      (node (ref "M_1") (pin "13") (pinfunction "R1In_13") (pintype "power_in"))
    )
    (net (code "103") (name "/RS232_TX") (class "Default")
      (node (ref "M1") (pin "2") (pinfunction "2_2") (pintype "passive"))
      (node (ref "M_1") (pin "14") (pinfunction "T1Out_14") (pintype "power_in"))
    )
    (net (code "104") (name "/SCL") (class "Default")
      (node (ref "*1") (pin "95") (pinfunction "PB6_95") (pintype "passive"))
      (node (ref "I2C") (pin "2") (pinfunction "2_2") (pintype "passive"))
      (node (ref "R18") (pin "2") (pinfunction "2_2") (pintype "passive"))
    )
    (net (code "105") (name "/SDA") (class "Default")
      (node (ref "*1") (pin "94") (pinfunction "PB7_94") (pintype "passive"))
      (node (ref "I2C") (pin "3") (pinfunction "3_3") (pintype "passive"))
      (node (ref "R19") (pin "2") (pinfunction "2_2") (pintype "passive"))
    )
    (net (code "106") (name "/SPI_MISO") (class "Default")
      (node (ref "*1") (pin "33") (pinfunction "PA6_33") (pintype "passive"))
      (node (ref "SPI") (pin "2") (pinfunction "2_2") (pintype "passive"))
    )
    (net (code "107") (name "/SPI_MOSI") (class "Default")
      (node (ref "*1") (pin "36") (pinfunction "PA7_36") (pintype "passive"))
      (node (ref "SPI") (pin "3") (pinfunction "3_3") (pintype "passive"))
    )
    (net (code "108") (name "/SPI_NSS") (class "Default")
      (node (ref "*1") (pin "31") (pinfunction "PA4_31") (pintype "passive"))
      (node (ref "SPI") (pin "5") (pinfunction "5_5") (pintype "passive"))
    )
    (net (code "109") (name "/SPI_SCK") (class "Default")
      (node (ref "*1") (pin "34") (pinfunction "PA5_34") (pintype "passive"))
      (node (ref "SPI") (pin "4") (pinfunction "4_4") (pintype "passive"))
    )
    (net (code "110") (name "/USART1_RX") (class "Default")
      (node (ref "*1") (pin "62") (pinfunction "PA10_62") (pintype "passive"))
      (node (ref "M_1") (pin "12") (pinfunction "R1Out_12") (pintype "power_in"))
    )
    (net (code "111") (name "/USART1_TX") (class "Default")
      (node (ref "*1") (pin "63") (pinfunction "PA9_63") (pintype "passive"))
      (node (ref "M_1") (pin "11") (pinfunction "T1In_11") (pintype "power_in"))
    )
    (net (code "112") (name "/USART2_RX") (class "Default")
      (node (ref "*1") (pin "108") (pinfunction "PD6_108") (pintype "passive"))
      (node (ref "UART2") (pin "3") (pinfunction "3_3") (pintype "passive"))
    )
    (net (code "113") (name "/USART2_TX") (class "Default")
      (node (ref "*1") (pin "107") (pinfunction "PD5_107") (pintype "passive"))
      (node (ref "UART2") (pin "4") (pinfunction "4_4") (pintype "passive"))
    )
    (net (code "114") (name "/USART3_RX") (class "Default")
      (node (ref "*1") (pin "116") (pinfunction "PC11_116") (pintype "passive"))
      (node (ref "UART3") (pin "3") (pinfunction "3_3") (pintype "passive"))
    )
    (net (code "115") (name "/USART3_TX") (class "Default")
      (node (ref "*1") (pin "115") (pinfunction "PC10_115") (pintype "passive"))
      (node (ref "UART3") (pin "4") (pinfunction "4_4") (pintype "passive"))
    )
    (net (code "116") (name "/USART6_RX") (class "Default")
      (node (ref "*1") (pin "67") (pinfunction "PC7_67") (pintype "passive"))
      (node (ref "M_2") (pin "1") (pinfunction "RO_1") (pintype "passive"))
    )
    (net (code "117") (name "/USART6_TX") (class "Default")
      (node (ref "*1") (pin "68") (pinfunction "PC6_68") (pintype "passive"))
      (node (ref "M_2") (pin "4") (pinfunction "DI_4") (pintype "passive"))
    )
    (net (code "118") (name "3.3V") (class "Default")
      (node (ref "*1") (pin "32") (pinfunction "3V3_32") (pintype "passive"))
      (node (ref "3.3V") (pin "1") (pinfunction "1_1") (pintype "passive"))
      (node (ref "3.3V") (pin "2") (pinfunction "2_2") (pintype "passive"))
      (node (ref "3.3V") (pin "3") (pinfunction "3_3") (pintype "passive"))
      (node (ref "3.3V") (pin "4") (pinfunction "4_4") (pintype "passive"))
      (node (ref "3.3V") (pin "5") (pinfunction "5_5") (pintype "passive"))
      (node (ref "3.3V") (pin "6") (pinfunction "6_6") (pintype "passive"))
      (node (ref "I2C") (pin "1") (pinfunction "1_1") (pintype "passive"))
      (node (ref "R18") (pin "1") (pinfunction "1_1") (pintype "passive"))
      (node (ref "R19") (pin "1") (pinfunction "1_1") (pintype "passive"))
      (node (ref "SPI") (pin "1") (pinfunction "1_1") (pintype "passive"))
    )
    (net (code "119") (name "5V") (class "Default")
      (node (ref "*1") (pin "30") (pinfunction "5V_30") (pintype "passive"))
      (node (ref "5V") (pin "1") (pinfunction "1_1") (pintype "passive"))
      (node (ref "5V") (pin "2") (pinfunction "2_2") (pintype "passive"))
      (node (ref "5V") (pin "3") (pinfunction "3_3") (pintype "passive"))
      (node (ref "5V") (pin "4") (pinfunction "4_4") (pintype "passive"))
      (node (ref "5V") (pin "5") (pinfunction "5_5") (pintype "passive"))
      (node (ref "5V") (pin "6") (pinfunction "6_6") (pintype "passive"))
      (node (ref "C10") (pin "1") (pinfunction "1_1") (pintype "passive"))
      (node (ref "C12") (pin "1") (pinfunction "1_1") (pintype "passive"))
      (node (ref "C6") (pin "1") (pinfunction "1_1") (pintype "passive"))
      (node (ref "C8") (pin "2") (pinfunction "2_2") (pintype "passive"))
      (node (ref "C9") (pin "2") (pinfunction "2_2") (pintype "passive"))
      (node (ref "L2") (pin "2") (pinfunction "2_2") (pintype "passive"))
      (node (ref "M_1") (pin "16") (pinfunction "Vcc_16") (pintype "power_in"))
      (node (ref "M_2") (pin "8") (pinfunction "VCC_8") (pintype "passive"))
      (node (ref "R14") (pin "2") (pinfunction "2_2") (pintype "passive"))
      (node (ref "R21") (pin "2") (pinfunction "2_2") (pintype "passive"))
      (node (ref "TJA1") (pin "3") (pinfunction "Vcc_3") (pintype "passive"))
      (node (ref "UART2") (pin "1") (pinfunction "1_1") (pintype "passive"))
      (node (ref "UART3") (pin "1") (pinfunction "1_1") (pintype "passive"))
    )
    (net (code "120") (name "24V") (class "Default")
      (node (ref "ALL1") (pin "1") (pinfunction "1_1") (pintype "passive"))
      (node (ref "C1") (pin "1") (pinfunction "1_1") (pintype "passive"))
      (node (ref "C2") (pin "2") (pinfunction "2_2") (pintype "passive"))
      (node (ref "D1") (pin "K") (pinfunction "2_K") (pintype "passive"))
      (node (ref "R10") (pin "1") (pinfunction "1_1") (pintype "passive"))
    )
    (net (code "121") (name "GND") (class "Default")
      (node (ref "*1") (pin "29") (pinfunction "GND_29") (pintype "passive"))
      (node (ref "GND") (pin "1") (pinfunction "1_1") (pintype "passive"))
      (node (ref "GND") (pin "2") (pinfunction "2_2") (pintype "passive"))
      (node (ref "GND") (pin "3") (pinfunction "3_3") (pintype "passive"))
      (node (ref "GND") (pin "4") (pinfunction "4_4") (pintype "passive"))
      (node (ref "GND") (pin "5") (pinfunction "5_5") (pintype "passive"))
      (node (ref "GND") (pin "6") (pinfunction "6_6") (pintype "passive"))
      (node (ref "I2C") (pin "4") (pinfunction "4_4") (pintype "passive"))
      (node (ref "R11") (pin "1") (pinfunction "1_1") (pintype "passive"))
      (node (ref "R12") (pin "1") (pinfunction "1_1") (pintype "passive"))
      (node (ref "R17") (pin "2") (pinfunction "2_2") (pintype "passive"))
      (node (ref "R4") (pin "1") (pinfunction "1_1") (pintype "passive"))
      (node (ref "R5") (pin "1") (pinfunction "1_1") (pintype "passive"))
      (node (ref "SPI") (pin "6") (pinfunction "6_6") (pintype "passive"))
      (node (ref "TJA1") (pin "2") (pinfunction "GND_2") (pintype "passive"))
      (node (ref "TJA1") (pin "8") (pinfunction "S_8") (pintype "passive"))
      (node (ref "UART2") (pin "2") (pinfunction "2_2") (pintype "passive"))
      (node (ref "UART3") (pin "2") (pinfunction "2_2") (pintype "passive"))
    )
    (net (code "122") (name "Net-(485_120-Pad1)") (class "Default")
      (node (ref "485_120") (pin "1") (pinfunction "1_1") (pintype "passive"))
      (node (ref "R22") (pin "1") (pinfunction "1_1") (pintype "passive"))
    )
    (net (code "123") (name "Net-(CAN_120-Pad1)") (class "Default")
      (node (ref "CAN_120") (pin "1") (pinfunction "1_1") (pintype "passive"))
      (node (ref "R3") (pin "1") (pinfunction "1_1") (pintype "passive"))
    )
    (net (code "124") (name "Net-(D1-1)") (class "Default")
      (node (ref "D1") (pin "A") (pinfunction "1_A") (pintype "passive"))
      (node (ref "L1") (pin "1") (pinfunction "1_1") (pintype "passive"))
      (node (ref "MC1") (pin "1") (pinfunction "SWC_1") (pintype "passive"))
    )
    (net (code "125") (name "Net-(D2-2)") (class "Default")
      (node (ref "C5") (pin "2") (pinfunction "2_2") (pintype "passive"))
      (node (ref "D2") (pin "K") (pinfunction "2_K") (pintype "passive"))
      (node (ref "L2") (pin "1") (pinfunction "1_1") (pintype "passive"))
      (node (ref "TPS1") (pin "8") (pinfunction "PH_8") (pintype "passive"))
    )
    (net (code "126") (name "Net-(MC1-COMP)") (class "Default")
      (node (ref "MC1") (pin "5") (pinfunction "COMP_5") (pintype "passive"))
      (node (ref "R10") (pin "2") (pinfunction "2_2") (pintype "passive"))
      (node (ref "R13") (pin "1") (pinfunction "1_1") (pintype "passive"))
    )
    (net (code "127") (name "Net-(MC1-IDC)") (class "Default")
      (node (ref "MC1") (pin "8") (pinfunction "IDC_8") (pintype "passive"))
      (node (ref "R8") (pin "2") (pinfunction "2_2") (pintype "passive"))
    )
    (net (code "128") (name "Net-(MC1-IPK)") (class "Default")
      (node (ref "L1") (pin "2") (pinfunction "2_2") (pintype "passive"))
      (node (ref "MC1") (pin "7") (pinfunction "IPK_7") (pintype "passive"))
      (node (ref "R8") (pin "1") (pinfunction "1_1") (pintype "passive"))
      (node (ref "R9") (pin "2") (pinfunction "2_2") (pintype "passive"))
    )
    (net (code "129") (name "Net-(MC1-TCAP)") (class "Default")
      (node (ref "C4") (pin "2") (pinfunction "2_2") (pintype "passive"))
      (node (ref "MC1") (pin "3") (pinfunction "TCAP_3") (pintype "passive"))
    )
    (net (code "130") (name "Net-(M_1-C1+)") (class "Default")
      (node (ref "C11") (pin "2") (pinfunction "2_2") (pintype "passive"))
      (node (ref "M_1") (pin "1") (pinfunction "C1+_1") (pintype "power_in"))
    )
    (net (code "131") (name "Net-(M_1-C1-)") (class "Default")
      (node (ref "C11") (pin "1") (pinfunction "1_1") (pintype "passive"))
      (node (ref "M_1") (pin "3") (pinfunction "C1-_3") (pintype "power_in"))
    )
    (net (code "132") (name "Net-(M_1-C2+)") (class "Default")
      (node (ref "C13") (pin "2") (pinfunction "2_2") (pintype "passive"))
      (node (ref "M_1") (pin "4") (pinfunction "C2+_4") (pintype "power_in"))
    )
    (net (code "133") (name "Net-(M_1-C2-)") (class "Default")
      (node (ref "C13") (pin "1") (pinfunction "1_1") (pintype "passive"))
      (node (ref "M_1") (pin "5") (pinfunction "C2-_5") (pintype "power_in"))
    )
    (net (code "134") (name "Net-(M_1-V+)") (class "Default")
      (node (ref "C9") (pin "1") (pinfunction "1_1") (pintype "passive"))
      (node (ref "M_1") (pin "2") (pinfunction "V+_2") (pintype "power_in"))
    )
    (net (code "135") (name "Net-(M_1-V-)") (class "Default")
      (node (ref "C14") (pin "2") (pinfunction "2_2") (pintype "passive"))
      (node (ref "M_1") (pin "6") (pinfunction "V-_6") (pintype "power_in"))
    )
    (net (code "136") (name "Net-(TPS1-BOOT)") (class "Default")
      (node (ref "C5") (pin "1") (pinfunction "1_1") (pintype "passive"))
      (node (ref "TPS1") (pin "1") (pinfunction "BOOT_1") (pintype "passive"))
    )
    (net (code "137") (name "Net-(TPS1-VSNS)") (class "Default")
      (node (ref "R14") (pin "1") (pinfunction "1_1") (pintype "passive"))
      (node (ref "R15") (pin "2") (pinfunction "2_2") (pintype "passive"))
      (node (ref "TPS1") (pin "4") (pinfunction "VSNS_4") (pintype "passive"))
    )
    (net (code "138") (name "Net-(VIN1-1)") (class "Default")
      (node (ref "R16") (pin "1") (pinfunction "1_1") (pintype "passive"))
      (node (ref "VIN1") (pin "A") (pinfunction "1_A") (pintype "passive"))
    )
    (net (code "139") (name "PGND") (class "Default")
      (node (ref "ALL1") (pin "2") (pinfunction "2_2") (pintype "passive"))
      (node (ref "C1") (pin "2") (pinfunction "2_2") (pintype "passive"))
      (node (ref "C10") (pin "2") (pinfunction "2_2") (pintype "passive"))
      (node (ref "C12") (pin "2") (pinfunction "2_2") (pintype "passive"))
      (node (ref "C14") (pin "1") (pinfunction "1_1") (pintype "passive"))
      (node (ref "C2") (pin "1") (pinfunction "1_1") (pintype "passive"))
      (node (ref "C3") (pin "1") (pinfunction "1_1") (pintype "passive"))
      (node (ref "C4") (pin "1") (pinfunction "1_1") (pintype "passive"))
      (node (ref "C6") (pin "2") (pinfunction "2_2") (pintype "passive"))
      (node (ref "C7") (pin "1") (pinfunction "1_1") (pintype "passive"))
      (node (ref "C8") (pin "1") (pinfunction "1_1") (pintype "passive"))
      (node (ref "D2") (pin "A") (pinfunction "1_A") (pintype "passive"))
      (node (ref "M1") (pin "3") (pinfunction "3_3") (pintype "passive"))
      (node (ref "MC1") (pin "2") (pinfunction "SWE_2") (pintype "passive"))
      (node (ref "MC1") (pin "4") (pinfunction "GND_4") (pintype "passive"))
      (node (ref "M_1") (pin "15") (pinfunction "Gnd_15") (pintype "power_in"))
      (node (ref "M_2") (pin "2") (pinfunction "RE-_2") (pintype "passive"))
      (node (ref "M_2") (pin "3") (pinfunction "DE_3") (pintype "passive"))
      (node (ref "M_2") (pin "5") (pinfunction "GND_5") (pintype "passive"))
      (node (ref "R13") (pin "2") (pinfunction "2_2") (pintype "passive"))
      (node (ref "R15") (pin "1") (pinfunction "1_1") (pintype "passive"))
      (node (ref "R17") (pin "1") (pinfunction "1_1") (pintype "passive"))
      (node (ref "R20") (pin "1") (pinfunction "1_1") (pintype "passive"))
      (node (ref "TPS1") (pin "6") (pinfunction "GND_6") (pintype "passive"))
      (node (ref "TPS1") (pin "9") (pinfunction "PWPD_9") (pintype "passive"))
      (node (ref "VIN") (pin "2") (pinfunction "2_2") (pintype "passive"))
      (node (ref "VIN") (pin "4") (pinfunction "4_4") (pintype "passive"))
      (node (ref "VIN") (pin "6") (pinfunction "6_6") (pintype "passive"))
      (node (ref "VIN1") (pin "K") (pinfunction "2_K") (pintype "passive"))
    )
    (net (code "140") (name "VIN") (class "Default")
      (node (ref "C3") (pin "2") (pinfunction "2_2") (pintype "passive"))
      (node (ref "C7") (pin "2") (pinfunction "2_2") (pintype "passive"))
      (node (ref "MC1") (pin "6") (pinfunction "VCC_6") (pintype "passive"))
      (node (ref "R16") (pin "2") (pinfunction "2_2") (pintype "passive"))
      (node (ref "R9") (pin "1") (pinfunction "1_1") (pintype "passive"))
      (node (ref "TPS1") (pin "7") (pinfunction "VIN_7") (pintype "passive"))
      (node (ref "VIN") (pin "1") (pinfunction "1_1") (pintype "passive"))
      (node (ref "VIN") (pin "3") (pinfunction "3_3") (pintype "passive"))
      (node (ref "VIN") (pin "5") (pinfunction "5_5") (pintype "passive"))
    )
    (net (code "141") (name "unconnected-(*1-CANH-Pad120)") (class "Default")
      (node (ref "*1") (pin "120") (pinfunction "CANH_120") (pintype "passive"))
    )
    (net (code "142") (name "unconnected-(*1-CANL-Pad119)") (class "Default")
      (node (ref "*1") (pin "119") (pinfunction "CANL_119") (pintype "passive"))
    )
    (net (code "143") (name "unconnected-(*1-NC-Pad1)") (class "Default")
      (node (ref "*1") (pin "1") (pinfunction "NC_1") (pintype "passive"))
    )
    (net (code "144") (name "unconnected-(*1-NC-Pad70)") (class "Default")
      (node (ref "*1") (pin "70") (pinfunction "NC_70") (pintype "passive"))
    )
    (net (code "145") (name "unconnected-(*1-NC-Pad89)") (class "Default")
      (node (ref "*1") (pin "89") (pinfunction "NC_89") (pintype "passive"))
    )
    (net (code "146") (name "unconnected-(*1-PA13-Pad59)") (class "Default")
      (node (ref "*1") (pin "59") (pinfunction "PA13_59") (pintype "passive"))
    )
    (net (code "147") (name "unconnected-(*1-PA14-Pad117)") (class "Default")
      (node (ref "*1") (pin "117") (pinfunction "PA14_117") (pintype "passive"))
    )
    (net (code "148") (name "unconnected-(*1-PB2-Pad39)") (class "Default")
      (node (ref "*1") (pin "39") (pinfunction "PB2_39") (pintype "passive"))
    )
    (net (code "149") (name "unconnected-(*1-RESET-Pad19)") (class "Default")
      (node (ref "*1") (pin "19") (pinfunction "RESET_19") (pintype "passive"))
    )
    (net (code "150") (name "unconnected-(*1-VREF+-Pad24)") (class "Default")
      (node (ref "*1") (pin "24") (pinfunction "VREF+_24") (pintype "passive"))
    )
    (net (code "151") (name "unconnected-(M_1-R2In-Pad8)") (class "Default")
      (node (ref "M_1") (pin "8") (pinfunction "R2In_8") (pintype "power_in"))
    )
    (net (code "152") (name "unconnected-(M_1-R2Out-Pad9)") (class "Default")
      (node (ref "M_1") (pin "9") (pinfunction "R2Out_9") (pintype "power_in"))
    )
    (net (code "153") (name "unconnected-(M_1-T2In-Pad10)") (class "Default")
      (node (ref "M_1") (pin "10") (pinfunction "T2In_10") (pintype "power_in"))
    )
    (net (code "154") (name "unconnected-(M_1-T2Out-Pad7)") (class "Default")
      (node (ref "M_1") (pin "7") (pinfunction "T2Out_7") (pintype "power_in"))
    )
    (net (code "155") (name "unconnected-(P1-Pad12)") (class "Default")
      (node (ref "P1") (pin "12") (pinfunction "12_12") (pintype "passive"))
    )
    (net (code "156") (name "unconnected-(P2-Pad11)") (class "Default")
      (node (ref "P2") (pin "11") (pinfunction "11_11") (pintype "passive"))
    )
    (net (code "157") (name "unconnected-(P2-Pad12)") (class "Default")
      (node (ref "P2") (pin "12") (pinfunction "12_12") (pintype "passive"))
    )
    (net (code "158") (name "unconnected-(P3-Pad11)") (class "Default")
      (node (ref "P3") (pin "11") (pinfunction "11_11") (pintype "passive"))
    )
    (net (code "159") (name "unconnected-(P3-Pad12)") (class "Default")
      (node (ref "P3") (pin "12") (pinfunction "12_12") (pintype "passive"))
    )
    (net (code "160") (name "unconnected-(P4-Pad11)") (class "Default")
      (node (ref "P4") (pin "11") (pinfunction "11_11") (pintype "passive"))
    )
    (net (code "161") (name "unconnected-(P4-Pad12)") (class "Default")
      (node (ref "P4") (pin "12") (pinfunction "12_12") (pintype "passive"))
    )
    (net (code "162") (name "unconnected-(P5-Pad1)") (class "Default")
      (node (ref "P5") (pin "1") (pinfunction "1_1") (pintype "passive"))
    )
    (net (code "163") (name "unconnected-(P6-Pad1)") (class "Default")
      (node (ref "P6") (pin "1") (pinfunction "1_1") (pintype "passive"))
    )
    (net (code "164") (name "unconnected-(P8-Pad11)") (class "Default")
      (node (ref "P8") (pin "11") (pinfunction "11_11") (pintype "passive"))
    )
    (net (code "165") (name "unconnected-(P8-Pad12)") (class "Default")
      (node (ref "P8") (pin "12") (pinfunction "12_12") (pintype "passive"))
    )
    (net (code "166") (name "unconnected-(TJA1-Vref-Pad5)") (class "Default")
      (node (ref "TJA1") (pin "5") (pinfunction "Vref_5") (pintype "passive"))
    )
    (net (code "167") (name "unconnected-(TPS1-ENA-Pad5)") (class "Default")
      (node (ref "TPS1") (pin "5") (pinfunction "ENA_5") (pintype "passive"))
    )
    (net (code "168") (name "unconnected-(TPS1-NC-Pad2)") (class "Default")
      (node (ref "TPS1") (pin "2") (pinfunction "NC_2") (pintype "passive"))
    )
    (net (code "169") (name "unconnected-(TPS1-NC-Pad3)") (class "Default")
      (node (ref "TPS1") (pin "3") (pinfunction "NC_3") (pintype "passive"))
    )
  )
)
